# MainBoard.net
KiCad netlist of a schematic drawn in EAGLE
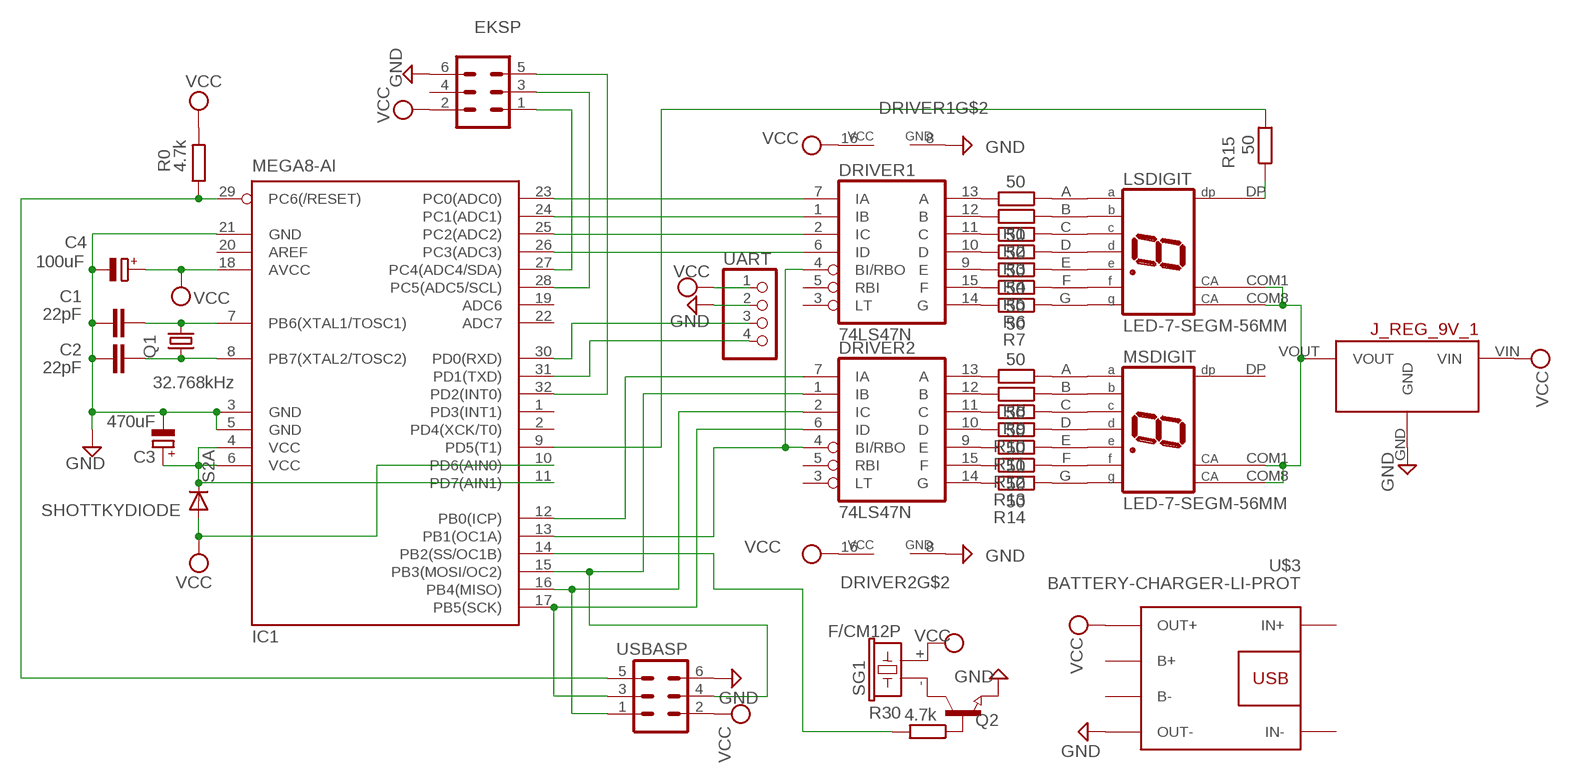
[diagram p0: schematic, sheet 1]

(export (version "E")
  (design (tool "Eeschema 10.0.6"))
  (components
    (comp (ref "C1")
      (value "22pF")
      (footprint "eagle-import:C2.5-2")
      (libsource (lib "eagle-import") (part "C2.5/2"))
    )
    (comp (ref "C2")
      (value "22pF")
      (footprint "eagle-import:C2.5-2")
      (libsource (lib "eagle-import") (part "C2.5/2"))
    )
    (comp (ref "C3")
      (value "470uF")
      (footprint "eagle-import:140CLH-1010")
      (libsource (lib "eagle-import") (part "CPOL-EU140CLH-1010"))
    )
    (comp (ref "C4")
      (value "100uF")
      (footprint "eagle-import:140CLH-1010")
      (libsource (lib "eagle-import") (part "CPOL-EU140CLH-1010"))
    )
    (comp (ref "DRIVER1")
      (value "74LS47N")
      (footprint "eagle-import:DIL16")
      (libsource (lib "eagle-import") (part "7447NLS"))
    )
    (comp (ref "DRIVER2")
      (value "74LS47N")
      (footprint "eagle-import:DIL16")
      (libsource (lib "eagle-import") (part "7447NLS"))
    )
    (comp (ref "EKSP")
      (value "ML6")
      (footprint "eagle-import:ML6")
      (libsource (lib "eagle-import") (part "ML6"))
    )
    (comp (ref "IC1")
      (value "MEGA8-AI")
      (footprint "eagle-import:TQFP32-08")
      (fields (field (name "MPN") "ATMEGA8-16AU"))
      (libsource (lib "eagle-import") (part "MEGA8-AI"))
    )
    (comp (ref "J_REG_9V_1")
      (value "9V_VOLTAGE_REGULATOR")
      (footprint "eagle-import:9V_VOLTAGE_REGULATOR")
      (libsource (lib "eagle-import") (part "9V_VOLTAGE_REGULATOR"))
    )
    (comp (ref "LSDIGIT")
      (value "LED-7-SEGM-56MM")
      (footprint "eagle-import:MYTHT")
      (libsource (lib "eagle-import") (part "LED-7-SEGM-56MM"))
    )
    (comp (ref "MSDIGIT")
      (value "LED-7-SEGM-56MM")
      (footprint "eagle-import:MYTHT")
      (libsource (lib "eagle-import") (part "LED-7-SEGM-56MM"))
    )
    (comp (ref "Q1")
      (value "32.768kHz")
      (footprint "eagle-import:TC26V")
      (libsource (lib "eagle-import") (part "CRYSTALTC26V"))
    )
    (comp (ref "Q2")
      (value "NPN-TRANSISTOR_SOT23")
      (footprint "eagle-import:SOT23")
      (libsource (lib "eagle-import") (part "NPN-TRANSISTOR_SOT23"))
    )
    (comp (ref "R0")
      (value "4.7k")
      (footprint "eagle-import:R01005")
      (libsource (lib "eagle-import") (part "R-EU_01005"))
    )
    (comp (ref "R1")
      (value "50")
      (footprint "eagle-import:R01005")
      (libsource (lib "eagle-import") (part "R-EU_01005"))
    )
    (comp (ref "R2")
      (value "50")
      (footprint "eagle-import:R01005")
      (libsource (lib "eagle-import") (part "R-EU_01005"))
    )
    (comp (ref "R3")
      (value "50")
      (footprint "eagle-import:R01005")
      (libsource (lib "eagle-import") (part "R-EU_01005"))
    )
    (comp (ref "R4")
      (value "50")
      (footprint "eagle-import:R01005")
      (libsource (lib "eagle-import") (part "R-EU_01005"))
    )
    (comp (ref "R5")
      (value "50")
      (footprint "eagle-import:R01005")
      (libsource (lib "eagle-import") (part "R-EU_01005"))
    )
    (comp (ref "R6")
      (value "50")
      (footprint "eagle-import:R01005")
      (libsource (lib "eagle-import") (part "R-EU_01005"))
    )
    (comp (ref "R7")
      (value "50")
      (footprint "eagle-import:R01005")
      (libsource (lib "eagle-import") (part "R-EU_01005"))
    )
    (comp (ref "R8")
      (value "50")
      (footprint "eagle-import:R01005")
      (libsource (lib "eagle-import") (part "R-EU_01005"))
    )
    (comp (ref "R9")
      (value "50")
      (footprint "eagle-import:R01005")
      (libsource (lib "eagle-import") (part "R-EU_01005"))
    )
    (comp (ref "R10")
      (value "50")
      (footprint "eagle-import:R01005")
      (libsource (lib "eagle-import") (part "R-EU_01005"))
    )
    (comp (ref "R11")
      (value "50")
      (footprint "eagle-import:R01005")
      (libsource (lib "eagle-import") (part "R-EU_01005"))
    )
    (comp (ref "R12")
      (value "50")
      (footprint "eagle-import:R01005")
      (libsource (lib "eagle-import") (part "R-EU_01005"))
    )
    (comp (ref "R13")
      (value "50")
      (footprint "eagle-import:R01005")
      (libsource (lib "eagle-import") (part "R-EU_01005"))
    )
    (comp (ref "R14")
      (value "50")
      (footprint "eagle-import:R01005")
      (libsource (lib "eagle-import") (part "R-EU_01005"))
    )
    (comp (ref "R15")
      (value "50")
      (footprint "eagle-import:R01005")
      (libsource (lib "eagle-import") (part "R-EU_01005"))
    )
    (comp (ref "R30")
      (value "4.7k")
      (footprint "eagle-import:R01005")
      (libsource (lib "eagle-import") (part "R-EU_01005"))
    )
    (comp (ref "SG1")
      (value "F/CM12P")
      (footprint "eagle-import:F_CM12P")
      (libsource (lib "eagle-import") (part "F/CM12P"))
    )
    (comp (ref "SHOTTKYDIODE")
      (value "S2A")
      (footprint "eagle-import:DO214AA")
      (fields (field (name "MF") "Fairchild"))
      (libsource (lib "eagle-import") (part "S2A"))
    )
    (comp (ref "U$3")
      (value "BATTERY-CHARGER-LI-PROT")
      (footprint "eagle-import:BATTERY-CHARGER-LI-PROT")
      (libsource (lib "eagle-import") (part "BATTERY-CHARGER-LI-PROT"))
    )
    (comp (ref "UART")
      (value "PINHD-1X4")
      (footprint "eagle-import:1X04")
      (libsource (lib "eagle-import") (part "PINHD-1X4"))
    )
    (comp (ref "USBASP")
      (value "ML6")
      (footprint "eagle-import:ML6")
      (libsource (lib "eagle-import") (part "ML6"))
    )
  )
  (nets
    (net (code "1") (name "GND") (class "Default")
      (node (ref "C1") (pin "1") (pinfunction "1_1") (pintype "passive"))
      (node (ref "C2") (pin "1") (pinfunction "1_1") (pintype "passive"))
      (node (ref "C3") (pin "-") (pinfunction "-_-") (pintype "passive"))
      (node (ref "C4") (pin "-") (pinfunction "-_-") (pintype "passive"))
      (node (ref "DRIVER1") (pin "8") (pinfunction "GND_8") (pintype "power_in"))
      (node (ref "DRIVER2") (pin "8") (pinfunction "GND_8") (pintype "power_in"))
      (node (ref "EKSP") (pin "6") (pinfunction "6_6") (pintype "passive"))
      (node (ref "IC1") (pin "21") (pinfunction "GND_21") (pintype "power_in"))
      (node (ref "IC1") (pin "3") (pinfunction "GND_3") (pintype "power_in"))
      (node (ref "IC1") (pin "5") (pinfunction "GND_5") (pintype "power_in"))
      (node (ref "J_REG_9V_1") (pin "GND") (pinfunction "GND_GND") (pintype "bidirectional"))
      (node (ref "Q2") (pin "2") (pinfunction "E_2") (pintype "passive"))
      (node (ref "U$3") (pin "OUT-") (pinfunction "OUT-_OUT-") (pintype "bidirectional"))
      (node (ref "UART") (pin "2") (pinfunction "2_2") (pintype "passive"))
      (node (ref "USBASP") (pin "6") (pinfunction "6_6") (pintype "passive"))
    )
    (net (code "2") (name "Net-(DRIVER1A-A)") (class "Default")
      (node (ref "DRIVER1") (pin "13") (pinfunction "A_13") (pintype "output"))
      (node (ref "R1") (pin "2") (pinfunction "2_2") (pintype "passive"))
    )
    (net (code "3") (name "Net-(DRIVER1A-B)") (class "Default")
      (node (ref "DRIVER1") (pin "12") (pinfunction "B_12") (pintype "output"))
      (node (ref "R2") (pin "2") (pinfunction "2_2") (pintype "passive"))
    )
    (net (code "4") (name "Net-(DRIVER1A-BI{slash}RBO)") (class "Default")
      (node (ref "DRIVER1") (pin "4") (pinfunction "BI/RBO_4") (pintype "input"))
      (node (ref "DRIVER2") (pin "4") (pinfunction "BI/RBO_4") (pintype "input"))
      (node (ref "IC1") (pin "13") (pinfunction "PB1(OC1A)_13") (pintype "bidirectional"))
    )
    (net (code "5") (name "Net-(DRIVER1A-C)") (class "Default")
      (node (ref "DRIVER1") (pin "11") (pinfunction "C_11") (pintype "output"))
      (node (ref "R3") (pin "2") (pinfunction "2_2") (pintype "passive"))
    )
    (net (code "6") (name "Net-(DRIVER1A-D)") (class "Default")
      (node (ref "DRIVER1") (pin "10") (pinfunction "D_10") (pintype "output"))
      (node (ref "R4") (pin "2") (pinfunction "2_2") (pintype "passive"))
    )
    (net (code "7") (name "Net-(DRIVER1A-E)") (class "Default")
      (node (ref "DRIVER1") (pin "9") (pinfunction "E_9") (pintype "output"))
      (node (ref "R5") (pin "2") (pinfunction "2_2") (pintype "passive"))
    )
    (net (code "8") (name "Net-(DRIVER1A-F)") (class "Default")
      (node (ref "DRIVER1") (pin "15") (pinfunction "F_15") (pintype "output"))
      (node (ref "R6") (pin "2") (pinfunction "2_2") (pintype "passive"))
    )
    (net (code "9") (name "Net-(DRIVER1A-G)") (class "Default")
      (node (ref "DRIVER1") (pin "14") (pinfunction "G_14") (pintype "output"))
      (node (ref "R7") (pin "2") (pinfunction "2_2") (pintype "passive"))
    )
    (net (code "10") (name "Net-(DRIVER1A-IA)") (class "Default")
      (node (ref "DRIVER1") (pin "7") (pinfunction "IA_7") (pintype "input"))
      (node (ref "IC1") (pin "23") (pinfunction "PC0(ADC0)_23") (pintype "bidirectional"))
    )
    (net (code "11") (name "Net-(DRIVER1A-IB)") (class "Default")
      (node (ref "DRIVER1") (pin "1") (pinfunction "IB_1") (pintype "input"))
      (node (ref "IC1") (pin "24") (pinfunction "PC1(ADC1)_24") (pintype "bidirectional"))
    )
    (net (code "12") (name "Net-(DRIVER1A-IC)") (class "Default")
      (node (ref "DRIVER1") (pin "2") (pinfunction "IC_2") (pintype "input"))
      (node (ref "IC1") (pin "25") (pinfunction "PC2(ADC2)_25") (pintype "bidirectional"))
    )
    (net (code "13") (name "Net-(DRIVER1A-ID)") (class "Default")
      (node (ref "DRIVER1") (pin "6") (pinfunction "ID_6") (pintype "input"))
      (node (ref "IC1") (pin "26") (pinfunction "PC3(ADC3)_26") (pintype "bidirectional"))
    )
    (net (code "14") (name "Net-(DRIVER2A-A)") (class "Default")
      (node (ref "DRIVER2") (pin "13") (pinfunction "A_13") (pintype "output"))
      (node (ref "R8") (pin "2") (pinfunction "2_2") (pintype "passive"))
    )
    (net (code "15") (name "Net-(DRIVER2A-B)") (class "Default")
      (node (ref "DRIVER2") (pin "12") (pinfunction "B_12") (pintype "output"))
      (node (ref "R9") (pin "2") (pinfunction "2_2") (pintype "passive"))
    )
    (net (code "16") (name "Net-(DRIVER2A-C)") (class "Default")
      (node (ref "DRIVER2") (pin "11") (pinfunction "C_11") (pintype "output"))
      (node (ref "R10") (pin "2") (pinfunction "2_2") (pintype "passive"))
    )
    (net (code "17") (name "Net-(DRIVER2A-D)") (class "Default")
      (node (ref "DRIVER2") (pin "10") (pinfunction "D_10") (pintype "output"))
      (node (ref "R11") (pin "2") (pinfunction "2_2") (pintype "passive"))
    )
    (net (code "18") (name "Net-(DRIVER2A-E)") (class "Default")
      (node (ref "DRIVER2") (pin "9") (pinfunction "E_9") (pintype "output"))
      (node (ref "R12") (pin "2") (pinfunction "2_2") (pintype "passive"))
    )
    (net (code "19") (name "Net-(DRIVER2A-F)") (class "Default")
      (node (ref "DRIVER2") (pin "15") (pinfunction "F_15") (pintype "output"))
      (node (ref "R13") (pin "2") (pinfunction "2_2") (pintype "passive"))
    )
    (net (code "20") (name "Net-(DRIVER2A-G)") (class "Default")
      (node (ref "DRIVER2") (pin "14") (pinfunction "G_14") (pintype "output"))
      (node (ref "R14") (pin "2") (pinfunction "2_2") (pintype "passive"))
    )
    (net (code "21") (name "Net-(DRIVER2A-IA)") (class "Default")
      (node (ref "DRIVER2") (pin "7") (pinfunction "IA_7") (pintype "input"))
      (node (ref "IC1") (pin "12") (pinfunction "PB0(ICP)_12") (pintype "bidirectional"))
    )
    (net (code "22") (name "Net-(DRIVER2A-IB)") (class "Default")
      (node (ref "DRIVER2") (pin "1") (pinfunction "IB_1") (pintype "input"))
      (node (ref "IC1") (pin "15") (pinfunction "PB3(MOSI/OC2)_15") (pintype "bidirectional"))
      (node (ref "USBASP") (pin "4") (pinfunction "4_4") (pintype "passive"))
    )
    (net (code "23") (name "Net-(DRIVER2A-IC)") (class "Default")
      (node (ref "DRIVER2") (pin "2") (pinfunction "IC_2") (pintype "input"))
      (node (ref "IC1") (pin "16") (pinfunction "PB4(MISO)_16") (pintype "bidirectional"))
      (node (ref "USBASP") (pin "1") (pinfunction "1_1") (pintype "passive"))
    )
    (net (code "24") (name "Net-(DRIVER2A-ID)") (class "Default")
      (node (ref "DRIVER2") (pin "6") (pinfunction "ID_6") (pintype "input"))
      (node (ref "IC1") (pin "17") (pinfunction "PB5(SCK)_17") (pintype "bidirectional"))
      (node (ref "USBASP") (pin "3") (pinfunction "3_3") (pintype "passive"))
    )
    (net (code "25") (name "Net-(IC1-PB2(SS{slash}OC1B))") (class "Default")
      (node (ref "IC1") (pin "14") (pinfunction "PB2(SS/OC1B)_14") (pintype "bidirectional"))
      (node (ref "R30") (pin "2") (pinfunction "2_2") (pintype "passive"))
    )
    (net (code "26") (name "Net-(IC1-PB6(XTAL1{slash}TOSC1))") (class "Default")
      (node (ref "C1") (pin "2") (pinfunction "2_2") (pintype "passive"))
      (node (ref "IC1") (pin "7") (pinfunction "PB6(XTAL1/TOSC1)_7") (pintype "bidirectional"))
      (node (ref "Q1") (pin "2") (pinfunction "2_2") (pintype "passive"))
    )
    (net (code "27") (name "Net-(IC1-PB7(XTAL2{slash}TOSC2))") (class "Default")
      (node (ref "C2") (pin "2") (pinfunction "2_2") (pintype "passive"))
      (node (ref "IC1") (pin "8") (pinfunction "PB7(XTAL2/TOSC2)_8") (pintype "bidirectional"))
      (node (ref "Q1") (pin "1") (pinfunction "1_1") (pintype "passive"))
    )
    (net (code "28") (name "Net-(IC1-PC4(ADC4{slash}SDA))") (class "Default")
      (node (ref "EKSP") (pin "1") (pinfunction "1_1") (pintype "passive"))
      (node (ref "IC1") (pin "27") (pinfunction "PC4(ADC4/SDA)_27") (pintype "bidirectional"))
    )
    (net (code "29") (name "Net-(IC1-PC5(ADC5{slash}SCL))") (class "Default")
      (node (ref "EKSP") (pin "3") (pinfunction "3_3") (pintype "passive"))
      (node (ref "IC1") (pin "28") (pinfunction "PC5(ADC5/SCL)_28") (pintype "bidirectional"))
    )
    (net (code "30") (name "Net-(IC1-PC6({slash}RESET))") (class "Default")
      (node (ref "IC1") (pin "29") (pinfunction "PC6(/RESET)_29") (pintype "bidirectional"))
      (node (ref "R0") (pin "1") (pinfunction "1_1") (pintype "passive"))
      (node (ref "USBASP") (pin "5") (pinfunction "5_5") (pintype "passive"))
    )
    (net (code "31") (name "Net-(IC1-PD0(RXD))") (class "Default")
      (node (ref "IC1") (pin "30") (pinfunction "PD0(RXD)_30") (pintype "bidirectional"))
      (node (ref "UART") (pin "3") (pinfunction "3_3") (pintype "passive"))
    )
    (net (code "32") (name "Net-(IC1-PD1(TXD))") (class "Default")
      (node (ref "IC1") (pin "31") (pinfunction "PD1(TXD)_31") (pintype "bidirectional"))
      (node (ref "UART") (pin "4") (pinfunction "4_4") (pintype "passive"))
    )
    (net (code "33") (name "Net-(IC1-PD2(INT0))") (class "Default")
      (node (ref "EKSP") (pin "5") (pinfunction "5_5") (pintype "passive"))
      (node (ref "IC1") (pin "32") (pinfunction "PD2(INT0)_32") (pintype "bidirectional"))
    )
    (net (code "34") (name "Net-(IC1-PD5(T1))") (class "Default")
      (node (ref "IC1") (pin "9") (pinfunction "PD5(T1)_9") (pintype "bidirectional"))
      (node (ref "R15") (pin "2") (pinfunction "2_2") (pintype "passive"))
    )
    (net (code "35") (name "Net-(IC1-PD7(AIN1))") (class "Default")
      (node (ref "C3") (pin "+") (pinfunction "+_+") (pintype "passive"))
      (node (ref "IC1") (pin "11") (pinfunction "PD7(AIN1)_11") (pintype "bidirectional"))
      (node (ref "IC1") (pin "4") (pinfunction "VCC_4") (pintype "power_in"))
      (node (ref "IC1") (pin "6") (pinfunction "VCC_6") (pintype "power_in"))
      (node (ref "SHOTTKYDIODE") (pin "C") (pinfunction "C_C") (pintype "passive"))
    )
    (net (code "36") (name "Net-(LSDIGIT-CA1)") (class "Default")
      (node (ref "J_REG_9V_1") (pin "VOUT") (pinfunction "VOUT_VOUT") (pintype "bidirectional"))
      (node (ref "LSDIGIT") (pin "COM1") (pinfunction "CA1_COM1") (pintype "passive"))
      (node (ref "LSDIGIT") (pin "COM8") (pinfunction "CA8_COM8") (pintype "passive"))
      (node (ref "MSDIGIT") (pin "COM1") (pinfunction "CA1_COM1") (pintype "passive"))
      (node (ref "MSDIGIT") (pin "COM8") (pinfunction "CA8_COM8") (pintype "passive"))
    )
    (net (code "37") (name "Net-(LSDIGIT-PadA)") (class "Default")
      (node (ref "LSDIGIT") (pin "A") (pinfunction "A_A") (pintype "passive"))
      (node (ref "R1") (pin "1") (pinfunction "1_1") (pintype "passive"))
    )
    (net (code "38") (name "Net-(LSDIGIT-PadB)") (class "Default")
      (node (ref "LSDIGIT") (pin "B") (pinfunction "B_B") (pintype "passive"))
      (node (ref "R2") (pin "1") (pinfunction "1_1") (pintype "passive"))
    )
    (net (code "39") (name "Net-(LSDIGIT-PadC)") (class "Default")
      (node (ref "LSDIGIT") (pin "C") (pinfunction "C_C") (pintype "passive"))
      (node (ref "R3") (pin "1") (pinfunction "1_1") (pintype "passive"))
    )
    (net (code "40") (name "Net-(LSDIGIT-PadD)") (class "Default")
      (node (ref "LSDIGIT") (pin "D") (pinfunction "D_D") (pintype "passive"))
      (node (ref "R4") (pin "1") (pinfunction "1_1") (pintype "passive"))
    )
    (net (code "41") (name "Net-(LSDIGIT-PadDP)") (class "Default")
      (node (ref "LSDIGIT") (pin "DP") (pinfunction "DP_DP") (pintype "passive"))
      (node (ref "R15") (pin "1") (pinfunction "1_1") (pintype "passive"))
    )
    (net (code "42") (name "Net-(LSDIGIT-PadE)") (class "Default")
      (node (ref "LSDIGIT") (pin "E") (pinfunction "E_E") (pintype "passive"))
      (node (ref "R5") (pin "1") (pinfunction "1_1") (pintype "passive"))
    )
    (net (code "43") (name "Net-(LSDIGIT-PadF)") (class "Default")
      (node (ref "LSDIGIT") (pin "F") (pinfunction "F_F") (pintype "passive"))
      (node (ref "R6") (pin "1") (pinfunction "1_1") (pintype "passive"))
    )
    (net (code "44") (name "Net-(LSDIGIT-PadG)") (class "Default")
      (node (ref "LSDIGIT") (pin "G") (pinfunction "G_G") (pintype "passive"))
      (node (ref "R7") (pin "1") (pinfunction "1_1") (pintype "passive"))
    )
    (net (code "45") (name "Net-(MSDIGIT-PadA)") (class "Default")
      (node (ref "MSDIGIT") (pin "A") (pinfunction "A_A") (pintype "passive"))
      (node (ref "R8") (pin "1") (pinfunction "1_1") (pintype "passive"))
    )
    (net (code "46") (name "Net-(MSDIGIT-PadB)") (class "Default")
      (node (ref "MSDIGIT") (pin "B") (pinfunction "B_B") (pintype "passive"))
      (node (ref "R9") (pin "1") (pinfunction "1_1") (pintype "passive"))
    )
    (net (code "47") (name "Net-(MSDIGIT-PadC)") (class "Default")
      (node (ref "MSDIGIT") (pin "C") (pinfunction "C_C") (pintype "passive"))
      (node (ref "R10") (pin "1") (pinfunction "1_1") (pintype "passive"))
    )
    (net (code "48") (name "Net-(MSDIGIT-PadD)") (class "Default")
      (node (ref "MSDIGIT") (pin "D") (pinfunction "D_D") (pintype "passive"))
      (node (ref "R11") (pin "1") (pinfunction "1_1") (pintype "passive"))
    )
    (net (code "49") (name "Net-(MSDIGIT-PadE)") (class "Default")
      (node (ref "MSDIGIT") (pin "E") (pinfunction "E_E") (pintype "passive"))
      (node (ref "R12") (pin "1") (pinfunction "1_1") (pintype "passive"))
    )
    (net (code "50") (name "Net-(MSDIGIT-PadF)") (class "Default")
      (node (ref "MSDIGIT") (pin "F") (pinfunction "F_F") (pintype "passive"))
      (node (ref "R13") (pin "1") (pinfunction "1_1") (pintype "passive"))
    )
    (net (code "51") (name "Net-(MSDIGIT-PadG)") (class "Default")
      (node (ref "MSDIGIT") (pin "G") (pinfunction "G_G") (pintype "passive"))
      (node (ref "R14") (pin "1") (pinfunction "1_1") (pintype "passive"))
    )
    (net (code "52") (name "Net-(Q2-B)") (class "Default")
      (node (ref "Q2") (pin "1") (pinfunction "B_1") (pintype "passive"))
      (node (ref "R30") (pin "1") (pinfunction "1_1") (pintype "passive"))
    )
    (net (code "53") (name "Net-(Q2-C)") (class "Default")
      (node (ref "Q2") (pin "3") (pinfunction "C_3") (pintype "passive"))
      (node (ref "SG1") (pin "-") (pinfunction "2_-") (pintype "passive"))
    )
    (net (code "54") (name "VCC") (class "Default")
      (node (ref "C4") (pin "+") (pinfunction "+_+") (pintype "passive"))
      (node (ref "DRIVER1") (pin "16") (pinfunction "VCC_16") (pintype "power_in"))
      (node (ref "DRIVER2") (pin "16") (pinfunction "VCC_16") (pintype "power_in"))
      (node (ref "EKSP") (pin "2") (pinfunction "2_2") (pintype "passive"))
      (node (ref "IC1") (pin "10") (pinfunction "PD6(AIN0)_10") (pintype "bidirectional"))
      (node (ref "IC1") (pin "18") (pinfunction "AVCC_18") (pintype "power_in"))
      (node (ref "J_REG_9V_1") (pin "VIN") (pinfunction "VIN_VIN") (pintype "bidirectional"))
      (node (ref "R0") (pin "2") (pinfunction "2_2") (pintype "passive"))
      (node (ref "SG1") (pin "+") (pinfunction "1_+") (pintype "passive"))
      (node (ref "SHOTTKYDIODE") (pin "A") (pinfunction "A_A") (pintype "passive"))
      (node (ref "U$3") (pin "OUT+") (pinfunction "OUT+_OUT+") (pintype "bidirectional"))
      (node (ref "UART") (pin "1") (pinfunction "1_1") (pintype "passive"))
      (node (ref "USBASP") (pin "2") (pinfunction "2_2") (pintype "passive"))
    )
    (net (code "55") (name "unconnected-(DRIVER1A-LT-Pad3)") (class "Default")
      (node (ref "DRIVER1") (pin "3") (pinfunction "LT_3") (pintype "input"))
    )
    (net (code "56") (name "unconnected-(DRIVER1A-RBI-Pad5)") (class "Default")
      (node (ref "DRIVER1") (pin "5") (pinfunction "RBI_5") (pintype "input"))
    )
    (net (code "57") (name "unconnected-(DRIVER2A-LT-Pad3)") (class "Default")
      (node (ref "DRIVER2") (pin "3") (pinfunction "LT_3") (pintype "input"))
    )
    (net (code "58") (name "unconnected-(DRIVER2A-RBI-Pad5)") (class "Default")
      (node (ref "DRIVER2") (pin "5") (pinfunction "RBI_5") (pintype "input"))
    )
    (net (code "59") (name "unconnected-(EKSP-Pad4)") (class "Default")
      (node (ref "EKSP") (pin "4") (pinfunction "4_4") (pintype "passive"))
    )
    (net (code "60") (name "unconnected-(IC1-ADC6-Pad19)") (class "Default")
      (node (ref "IC1") (pin "19") (pinfunction "ADC6_19") (pintype "bidirectional"))
    )
    (net (code "61") (name "unconnected-(IC1-ADC7-Pad22)") (class "Default")
      (node (ref "IC1") (pin "22") (pinfunction "ADC7_22") (pintype "bidirectional"))
    )
    (net (code "62") (name "unconnected-(IC1-AREF-Pad20)") (class "Default")
      (node (ref "IC1") (pin "20") (pinfunction "AREF_20") (pintype "passive"))
    )
    (net (code "63") (name "unconnected-(IC1-PD3(INT1)-Pad1)") (class "Default")
      (node (ref "IC1") (pin "1") (pinfunction "PD3(INT1)_1") (pintype "bidirectional"))
    )
    (net (code "64") (name "unconnected-(IC1-PD4(XCK{slash}T0)-Pad2)") (class "Default")
      (node (ref "IC1") (pin "2") (pinfunction "PD4(XCK/T0)_2") (pintype "bidirectional"))
    )
    (net (code "65") (name "unconnected-(MSDIGIT-PadDP)") (class "Default")
      (node (ref "MSDIGIT") (pin "DP") (pinfunction "DP_DP") (pintype "passive"))
    )
    (net (code "66") (name "unconnected-(U$3-PadB+)") (class "Default")
      (node (ref "U$3") (pin "B+") (pinfunction "B+_B+") (pintype "bidirectional"))
    )
    (net (code "67") (name "unconnected-(U$3-PadB-)") (class "Default")
      (node (ref "U$3") (pin "B-") (pinfunction "B-_B-") (pintype "bidirectional"))
    )
    (net (code "68") (name "unconnected-(U$3-PadIN+)") (class "Default")
      (node (ref "U$3") (pin "IN+") (pinfunction "IN+_IN+") (pintype "bidirectional"))
    )
    (net (code "69") (name "unconnected-(U$3-PadIN-)") (class "Default")
      (node (ref "U$3") (pin "IN-") (pinfunction "IN-_IN-") (pintype "bidirectional"))
    )
  )
)
